# untitled.net
KiCad netlist of a schematic drawn in EAGLE
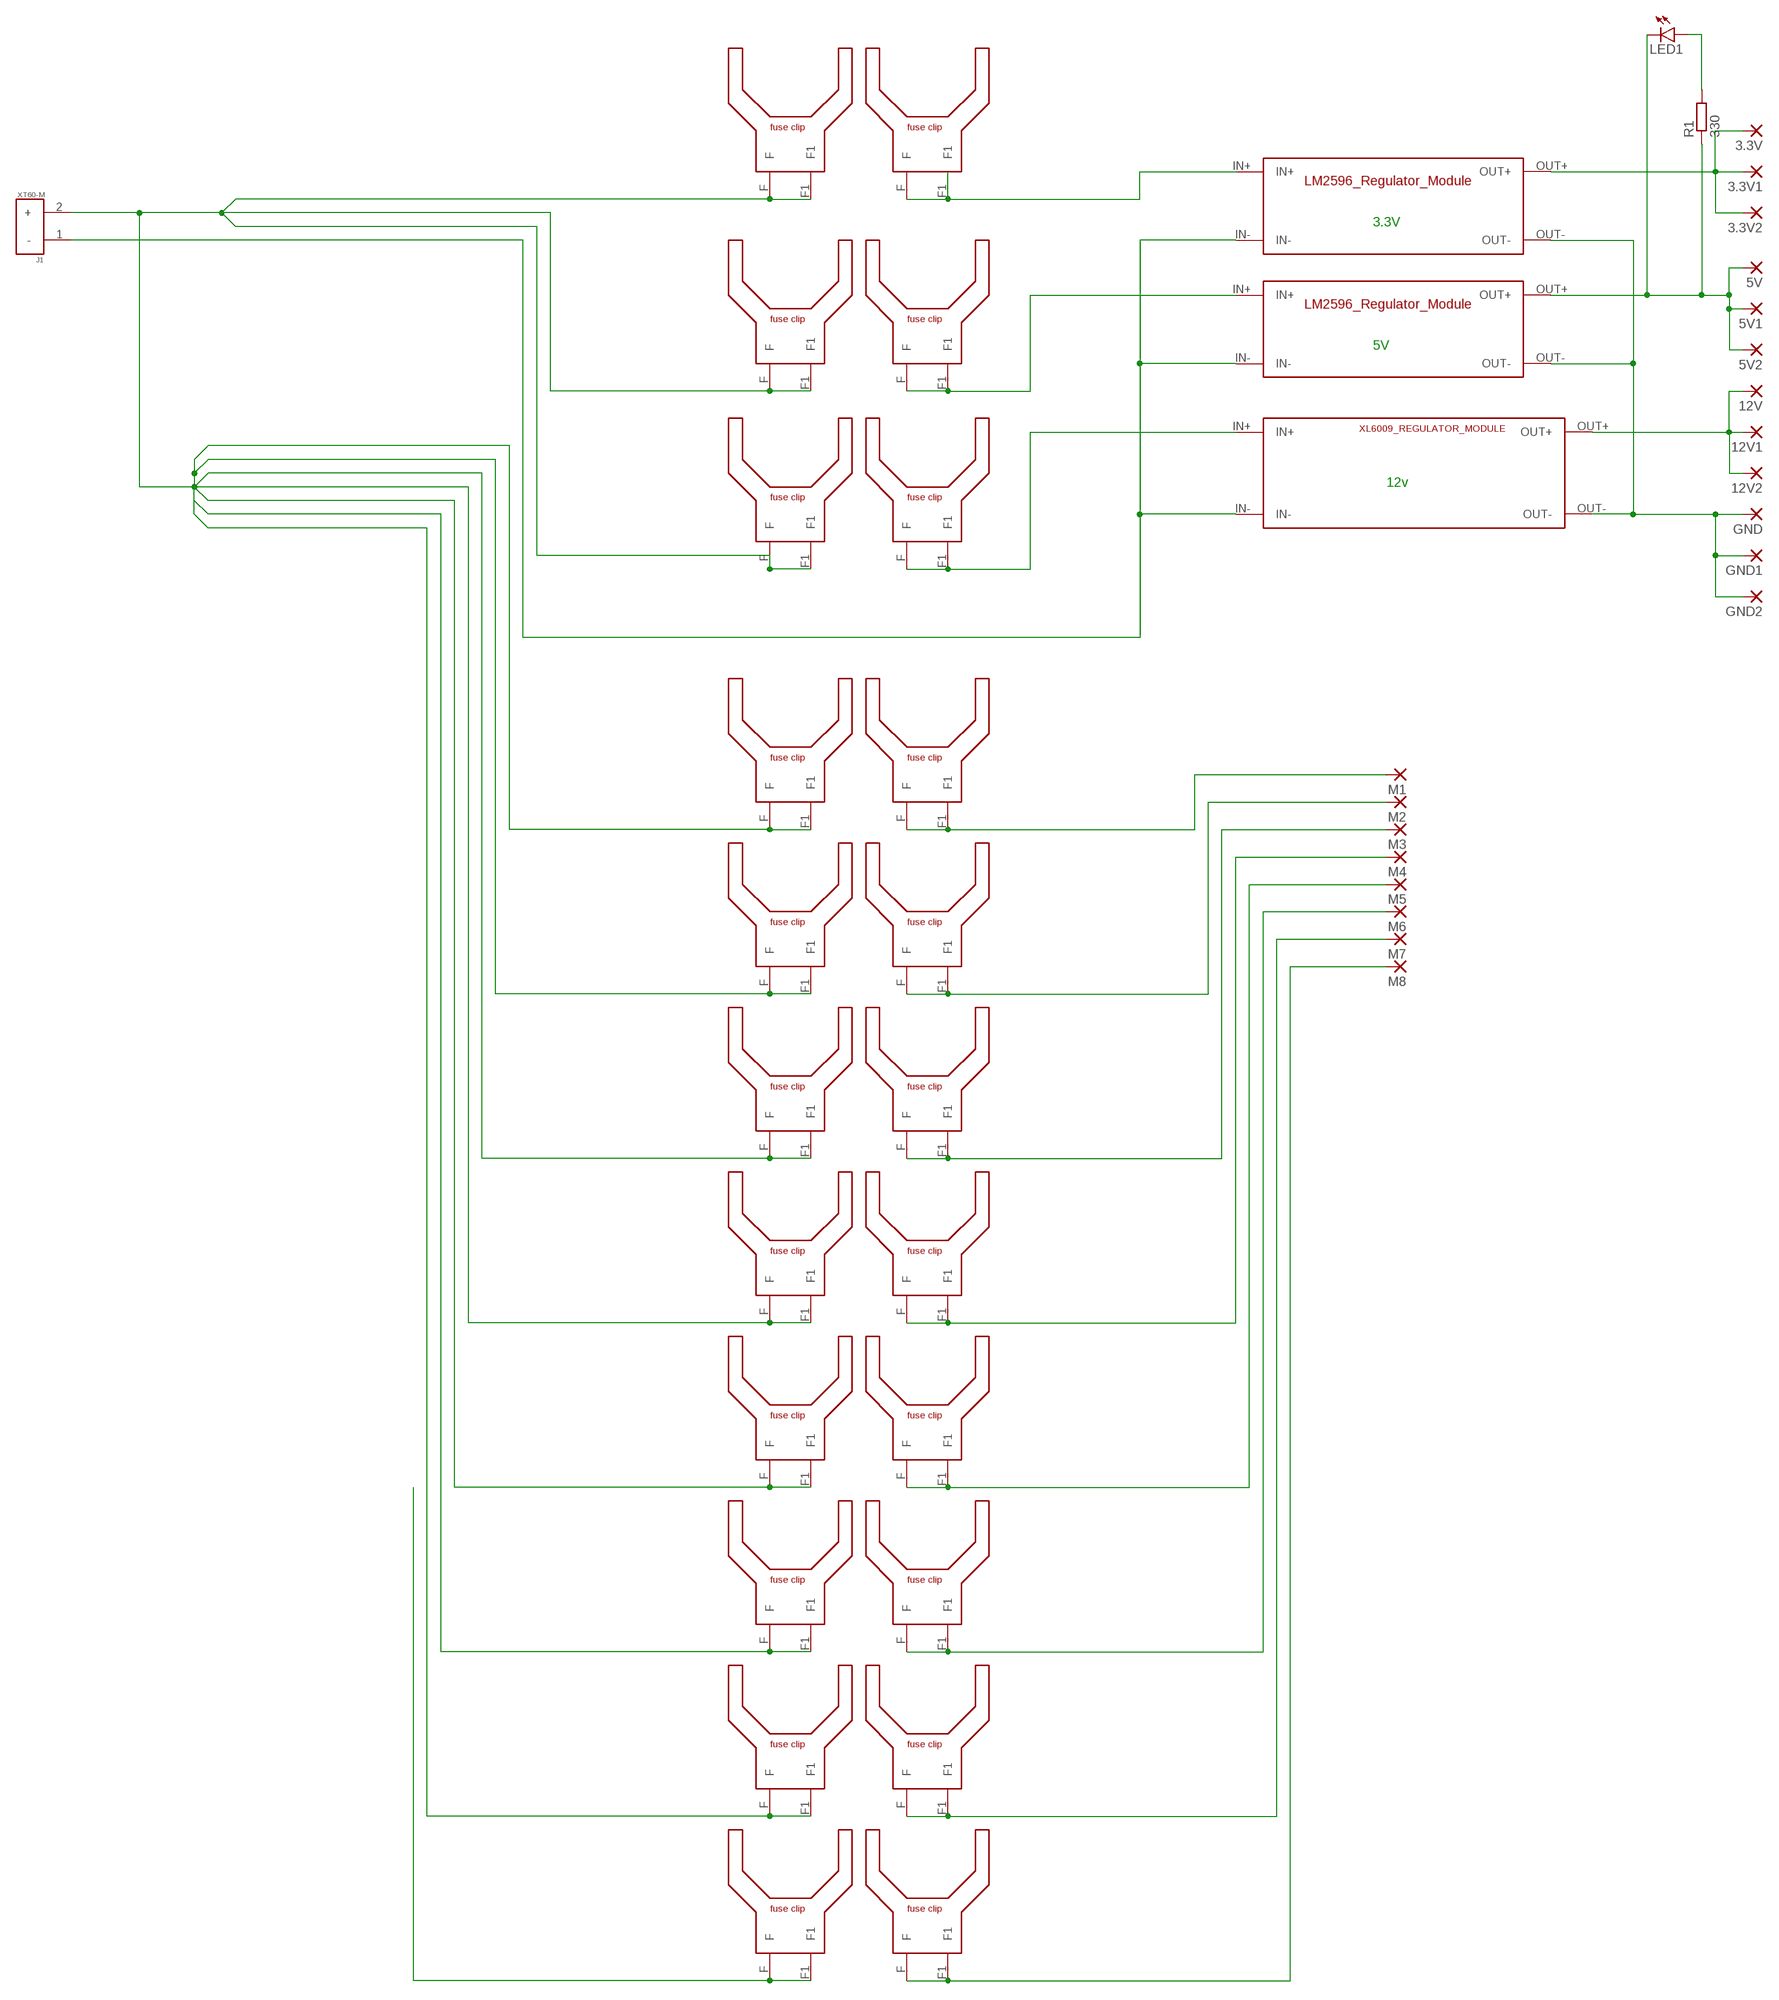
[diagram p0: schematic, sheet 1]

(export (version "E")
  (design (tool "Eeschema 10.0.6"))
  (components
    (comp (ref "3.3V")
      (value "SMD5")
      (footprint "eagle-import:SMD2,54-5,08")
      (libsource (lib "eagle-import") (part "SMD5"))
    )
    (comp (ref "3.3V1")
      (value "SMD5")
      (footprint "eagle-import:SMD2,54-5,08")
      (libsource (lib "eagle-import") (part "SMD5"))
    )
    (comp (ref "3.3V2")
      (value "SMD5")
      (footprint "eagle-import:SMD2,54-5,08")
      (libsource (lib "eagle-import") (part "SMD5"))
    )
    (comp (ref "5V")
      (value "SMD5")
      (footprint "eagle-import:SMD2,54-5,08")
      (libsource (lib "eagle-import") (part "SMD5"))
    )
    (comp (ref "5V1")
      (value "SMD5")
      (footprint "eagle-import:SMD2,54-5,08")
      (libsource (lib "eagle-import") (part "SMD5"))
    )
    (comp (ref "5V2")
      (value "SMD5")
      (footprint "eagle-import:SMD2,54-5,08")
      (libsource (lib "eagle-import") (part "SMD5"))
    )
    (comp (ref "12V")
      (value "SMD5")
      (footprint "eagle-import:SMD2,54-5,08")
      (libsource (lib "eagle-import") (part "SMD5"))
    )
    (comp (ref "12V1")
      (value "SMD5")
      (footprint "eagle-import:SMD2,54-5,08")
      (libsource (lib "eagle-import") (part "SMD5"))
    )
    (comp (ref "12V2")
      (value "SMD5")
      (footprint "eagle-import:SMD2,54-5,08")
      (libsource (lib "eagle-import") (part "SMD5"))
    )
    (comp (ref "GND")
      (value "SMD5")
      (footprint "eagle-import:SMD2,54-5,08")
      (libsource (lib "eagle-import") (part "SMD5"))
    )
    (comp (ref "GND1")
      (value "SMD5")
      (footprint "eagle-import:SMD2,54-5,08")
      (libsource (lib "eagle-import") (part "SMD5"))
    )
    (comp (ref "GND2")
      (value "SMD5")
      (footprint "eagle-import:SMD2,54-5,08")
      (libsource (lib "eagle-import") (part "SMD5"))
    )
    (comp (ref "J1")
      (value "XT60-M")
      (footprint "eagle-import:AMASS_XT60-M")
      (fields (field (name "MF") "AMASS"))
      (libsource (lib "eagle-import") (part "XT60-M"))
    )
    (comp (ref "LED1")
      (value "LED5MM")
      (footprint "eagle-import:LED5MM")
      (libsource (lib "eagle-import") (part "LED5MM"))
    )
    (comp (ref "M1")
      (value "SMD5")
      (footprint "eagle-import:SMD2,54-5,08")
      (libsource (lib "eagle-import") (part "SMD5"))
    )
    (comp (ref "M2")
      (value "SMD5")
      (footprint "eagle-import:SMD2,54-5,08")
      (libsource (lib "eagle-import") (part "SMD5"))
    )
    (comp (ref "M3")
      (value "SMD5")
      (footprint "eagle-import:SMD2,54-5,08")
      (libsource (lib "eagle-import") (part "SMD5"))
    )
    (comp (ref "M4")
      (value "SMD5")
      (footprint "eagle-import:SMD2,54-5,08")
      (libsource (lib "eagle-import") (part "SMD5"))
    )
    (comp (ref "M5")
      (value "SMD5")
      (footprint "eagle-import:SMD2,54-5,08")
      (libsource (lib "eagle-import") (part "SMD5"))
    )
    (comp (ref "M6")
      (value "SMD5")
      (footprint "eagle-import:SMD2,54-5,08")
      (libsource (lib "eagle-import") (part "SMD5"))
    )
    (comp (ref "M7")
      (value "SMD5")
      (footprint "eagle-import:SMD2,54-5,08")
      (libsource (lib "eagle-import") (part "SMD5"))
    )
    (comp (ref "M8")
      (value "SMD5")
      (footprint "eagle-import:SMD2,54-5,08")
      (libsource (lib "eagle-import") (part "SMD5"))
    )
    (comp (ref "R1")
      (value "330")
      (footprint "eagle-import:0207_10")
      (libsource (lib "eagle-import") (part "R-EU_0207/10"))
    )
    (comp (ref "U$1")
      (value "LM2596_MODULE")
      (footprint "eagle-import:LM2596_MODULE")
      (libsource (lib "eagle-import") (part "LM2596_MODULE"))
    )
    (comp (ref "U$2")
      (value "LM2596_MODULE")
      (footprint "eagle-import:LM2596_MODULE")
      (libsource (lib "eagle-import") (part "LM2596_MODULE"))
    )
    (comp (ref "U$3")
      (value "XL6009_MODULE")
      (footprint "eagle-import:XL6009_MODULE")
      (libsource (lib "eagle-import") (part "XL6009_MODULE"))
    )
    (comp (ref "U$4")
      (value "FUSE_HOLDER")
      (footprint "eagle-import:FUSE_HOLDER")
      (libsource (lib "eagle-import") (part "FUSE_HOLDER"))
    )
    (comp (ref "U$5")
      (value "FUSE_HOLDER")
      (footprint "eagle-import:FUSE_HOLDER")
      (libsource (lib "eagle-import") (part "FUSE_HOLDER"))
    )
    (comp (ref "U$6")
      (value "FUSE_HOLDER")
      (footprint "eagle-import:FUSE_HOLDER")
      (libsource (lib "eagle-import") (part "FUSE_HOLDER"))
    )
    (comp (ref "U$7")
      (value "FUSE_HOLDER")
      (footprint "eagle-import:FUSE_HOLDER")
      (libsource (lib "eagle-import") (part "FUSE_HOLDER"))
    )
    (comp (ref "U$8")
      (value "FUSE_HOLDER")
      (footprint "eagle-import:FUSE_HOLDER")
      (libsource (lib "eagle-import") (part "FUSE_HOLDER"))
    )
    (comp (ref "U$9")
      (value "FUSE_HOLDER")
      (footprint "eagle-import:FUSE_HOLDER")
      (libsource (lib "eagle-import") (part "FUSE_HOLDER"))
    )
    (comp (ref "U$10")
      (value "FUSE_HOLDER")
      (footprint "eagle-import:FUSE_HOLDER")
      (libsource (lib "eagle-import") (part "FUSE_HOLDER"))
    )
    (comp (ref "U$11")
      (value "FUSE_HOLDER")
      (footprint "eagle-import:FUSE_HOLDER")
      (libsource (lib "eagle-import") (part "FUSE_HOLDER"))
    )
    (comp (ref "U$12")
      (value "FUSE_HOLDER")
      (footprint "eagle-import:FUSE_HOLDER")
      (libsource (lib "eagle-import") (part "FUSE_HOLDER"))
    )
    (comp (ref "U$13")
      (value "FUSE_HOLDER")
      (footprint "eagle-import:FUSE_HOLDER")
      (libsource (lib "eagle-import") (part "FUSE_HOLDER"))
    )
    (comp (ref "U$14")
      (value "FUSE_HOLDER")
      (footprint "eagle-import:FUSE_HOLDER")
      (libsource (lib "eagle-import") (part "FUSE_HOLDER"))
    )
    (comp (ref "U$15")
      (value "FUSE_HOLDER")
      (footprint "eagle-import:FUSE_HOLDER")
      (libsource (lib "eagle-import") (part "FUSE_HOLDER"))
    )
    (comp (ref "U$16")
      (value "FUSE_HOLDER")
      (footprint "eagle-import:FUSE_HOLDER")
      (libsource (lib "eagle-import") (part "FUSE_HOLDER"))
    )
    (comp (ref "U$17")
      (value "FUSE_HOLDER")
      (footprint "eagle-import:FUSE_HOLDER")
      (libsource (lib "eagle-import") (part "FUSE_HOLDER"))
    )
    (comp (ref "U$18")
      (value "FUSE_HOLDER")
      (footprint "eagle-import:FUSE_HOLDER")
      (libsource (lib "eagle-import") (part "FUSE_HOLDER"))
    )
    (comp (ref "U$19")
      (value "FUSE_HOLDER")
      (footprint "eagle-import:FUSE_HOLDER")
      (libsource (lib "eagle-import") (part "FUSE_HOLDER"))
    )
    (comp (ref "U$20")
      (value "FUSE_HOLDER")
      (footprint "eagle-import:FUSE_HOLDER")
      (libsource (lib "eagle-import") (part "FUSE_HOLDER"))
    )
    (comp (ref "U$21")
      (value "FUSE_HOLDER")
      (footprint "eagle-import:FUSE_HOLDER")
      (libsource (lib "eagle-import") (part "FUSE_HOLDER"))
    )
    (comp (ref "U$22")
      (value "FUSE_HOLDER")
      (footprint "eagle-import:FUSE_HOLDER")
      (libsource (lib "eagle-import") (part "FUSE_HOLDER"))
    )
    (comp (ref "U$23")
      (value "FUSE_HOLDER")
      (footprint "eagle-import:FUSE_HOLDER")
      (libsource (lib "eagle-import") (part "FUSE_HOLDER"))
    )
    (comp (ref "U$24")
      (value "FUSE_HOLDER")
      (footprint "eagle-import:FUSE_HOLDER")
      (libsource (lib "eagle-import") (part "FUSE_HOLDER"))
    )
    (comp (ref "U$25")
      (value "FUSE_HOLDER")
      (footprint "eagle-import:FUSE_HOLDER")
      (libsource (lib "eagle-import") (part "FUSE_HOLDER"))
    )
  )
  (nets
    (net (code "1") (name "Net-(3.3V-P)") (class "Default")
      (node (ref "3.3V") (pin "1") (pinfunction "P_1") (pintype "passive"))
      (node (ref "3.3V1") (pin "1") (pinfunction "P_1") (pintype "passive"))
      (node (ref "3.3V2") (pin "1") (pinfunction "P_1") (pintype "passive"))
      (node (ref "U$1") (pin "OUT+") (pinfunction "OUT+_OUT+") (pintype "bidirectional"))
    )
    (net (code "2") (name "Net-(5V-P)") (class "Default")
      (node (ref "5V") (pin "1") (pinfunction "P_1") (pintype "passive"))
      (node (ref "5V1") (pin "1") (pinfunction "P_1") (pintype "passive"))
      (node (ref "5V2") (pin "1") (pinfunction "P_1") (pintype "passive"))
      (node (ref "LED1") (pin "K") (pinfunction "C_K") (pintype "passive"))
      (node (ref "R1") (pin "1") (pinfunction "1_1") (pintype "passive"))
      (node (ref "U$2") (pin "OUT+") (pinfunction "OUT+_OUT+") (pintype "bidirectional"))
    )
    (net (code "3") (name "Net-(12V-P)") (class "Default")
      (node (ref "12V") (pin "1") (pinfunction "P_1") (pintype "passive"))
      (node (ref "12V1") (pin "1") (pinfunction "P_1") (pintype "passive"))
      (node (ref "12V2") (pin "1") (pinfunction "P_1") (pintype "passive"))
      (node (ref "U$3") (pin "OUT+") (pinfunction "OUT+_OUT+") (pintype "bidirectional"))
    )
    (net (code "4") (name "Net-(GND-P)") (class "Default")
      (node (ref "GND") (pin "1") (pinfunction "P_1") (pintype "passive"))
      (node (ref "GND1") (pin "1") (pinfunction "P_1") (pintype "passive"))
      (node (ref "GND2") (pin "1") (pinfunction "P_1") (pintype "passive"))
      (node (ref "U$1") (pin "OUT-") (pinfunction "OUT-_OUT-") (pintype "bidirectional"))
      (node (ref "U$2") (pin "OUT-") (pinfunction "OUT-_OUT-") (pintype "bidirectional"))
      (node (ref "U$3") (pin "OUT-") (pinfunction "OUT-_OUT-") (pintype "bidirectional"))
    )
    (net (code "5") (name "Net-(J1-+)") (class "Default")
      (node (ref "J1") (pin "2") (pinfunction "+_2") (pintype "passive"))
      (node (ref "U$10") (pin "F") (pinfunction "F_F") (pintype "bidirectional"))
      (node (ref "U$10") (pin "F1") (pinfunction "F1_F1") (pintype "bidirectional"))
      (node (ref "U$12") (pin "F") (pinfunction "F_F") (pintype "bidirectional"))
      (node (ref "U$12") (pin "F1") (pinfunction "F1_F1") (pintype "bidirectional"))
      (node (ref "U$14") (pin "F") (pinfunction "F_F") (pintype "bidirectional"))
      (node (ref "U$14") (pin "F1") (pinfunction "F1_F1") (pintype "bidirectional"))
      (node (ref "U$16") (pin "F") (pinfunction "F_F") (pintype "bidirectional"))
      (node (ref "U$16") (pin "F1") (pinfunction "F1_F1") (pintype "bidirectional"))
      (node (ref "U$18") (pin "F") (pinfunction "F_F") (pintype "bidirectional"))
      (node (ref "U$18") (pin "F1") (pinfunction "F1_F1") (pintype "bidirectional"))
      (node (ref "U$20") (pin "F") (pinfunction "F_F") (pintype "bidirectional"))
      (node (ref "U$20") (pin "F1") (pinfunction "F1_F1") (pintype "bidirectional"))
      (node (ref "U$22") (pin "F") (pinfunction "F_F") (pintype "bidirectional"))
      (node (ref "U$22") (pin "F1") (pinfunction "F1_F1") (pintype "bidirectional"))
      (node (ref "U$5") (pin "F") (pinfunction "F_F") (pintype "bidirectional"))
      (node (ref "U$5") (pin "F1") (pinfunction "F1_F1") (pintype "bidirectional"))
      (node (ref "U$7") (pin "F") (pinfunction "F_F") (pintype "bidirectional"))
      (node (ref "U$7") (pin "F1") (pinfunction "F1_F1") (pintype "bidirectional"))
      (node (ref "U$9") (pin "F") (pinfunction "F_F") (pintype "bidirectional"))
      (node (ref "U$9") (pin "F1") (pinfunction "F1_F1") (pintype "bidirectional"))
    )
    (net (code "6") (name "Net-(J1--)") (class "Default")
      (node (ref "J1") (pin "1") (pinfunction "-_1") (pintype "passive"))
      (node (ref "U$1") (pin "IN-") (pinfunction "IN-_IN-") (pintype "bidirectional"))
      (node (ref "U$2") (pin "IN-") (pinfunction "IN-_IN-") (pintype "bidirectional"))
      (node (ref "U$3") (pin "IN-") (pinfunction "IN-_IN-") (pintype "bidirectional"))
    )
    (net (code "7") (name "Net-(LED1-PadA)") (class "Default")
      (node (ref "LED1") (pin "A") (pinfunction "A_A") (pintype "passive"))
      (node (ref "R1") (pin "2") (pinfunction "2_2") (pintype "passive"))
    )
    (net (code "8") (name "Net-(M1-P)") (class "Default")
      (node (ref "M1") (pin "1") (pinfunction "P_1") (pintype "passive"))
      (node (ref "U$11") (pin "F") (pinfunction "F_F") (pintype "bidirectional"))
      (node (ref "U$11") (pin "F1") (pinfunction "F1_F1") (pintype "bidirectional"))
    )
    (net (code "9") (name "Net-(M2-P)") (class "Default")
      (node (ref "M2") (pin "1") (pinfunction "P_1") (pintype "passive"))
      (node (ref "U$13") (pin "F") (pinfunction "F_F") (pintype "bidirectional"))
      (node (ref "U$13") (pin "F1") (pinfunction "F1_F1") (pintype "bidirectional"))
    )
    (net (code "10") (name "Net-(M3-P)") (class "Default")
      (node (ref "M3") (pin "1") (pinfunction "P_1") (pintype "passive"))
      (node (ref "U$15") (pin "F") (pinfunction "F_F") (pintype "bidirectional"))
      (node (ref "U$15") (pin "F1") (pinfunction "F1_F1") (pintype "bidirectional"))
    )
    (net (code "11") (name "Net-(M4-P)") (class "Default")
      (node (ref "M4") (pin "1") (pinfunction "P_1") (pintype "passive"))
      (node (ref "U$17") (pin "F") (pinfunction "F_F") (pintype "bidirectional"))
      (node (ref "U$17") (pin "F1") (pinfunction "F1_F1") (pintype "bidirectional"))
    )
    (net (code "12") (name "Net-(M5-P)") (class "Default")
      (node (ref "M5") (pin "1") (pinfunction "P_1") (pintype "passive"))
      (node (ref "U$19") (pin "F") (pinfunction "F_F") (pintype "bidirectional"))
      (node (ref "U$19") (pin "F1") (pinfunction "F1_F1") (pintype "bidirectional"))
    )
    (net (code "13") (name "Net-(M6-P)") (class "Default")
      (node (ref "M6") (pin "1") (pinfunction "P_1") (pintype "passive"))
      (node (ref "U$21") (pin "F") (pinfunction "F_F") (pintype "bidirectional"))
      (node (ref "U$21") (pin "F1") (pinfunction "F1_F1") (pintype "bidirectional"))
    )
    (net (code "14") (name "Net-(M7-P)") (class "Default")
      (node (ref "M7") (pin "1") (pinfunction "P_1") (pintype "passive"))
      (node (ref "U$23") (pin "F") (pinfunction "F_F") (pintype "bidirectional"))
      (node (ref "U$23") (pin "F1") (pinfunction "F1_F1") (pintype "bidirectional"))
    )
    (net (code "15") (name "Net-(M8-P)") (class "Default")
      (node (ref "M8") (pin "1") (pinfunction "P_1") (pintype "passive"))
      (node (ref "U$25") (pin "F") (pinfunction "F_F") (pintype "bidirectional"))
      (node (ref "U$25") (pin "F1") (pinfunction "F1_F1") (pintype "bidirectional"))
    )
    (net (code "16") (name "Net-(U$1-PadIN+)") (class "Default")
      (node (ref "U$1") (pin "IN+") (pinfunction "IN+_IN+") (pintype "bidirectional"))
      (node (ref "U$4") (pin "F") (pinfunction "F_F") (pintype "bidirectional"))
      (node (ref "U$4") (pin "F1") (pinfunction "F1_F1") (pintype "bidirectional"))
    )
    (net (code "17") (name "Net-(U$2-PadIN+)") (class "Default")
      (node (ref "U$2") (pin "IN+") (pinfunction "IN+_IN+") (pintype "bidirectional"))
      (node (ref "U$6") (pin "F") (pinfunction "F_F") (pintype "bidirectional"))
      (node (ref "U$6") (pin "F1") (pinfunction "F1_F1") (pintype "bidirectional"))
    )
    (net (code "18") (name "Net-(U$3-PadIN+)") (class "Default")
      (node (ref "U$3") (pin "IN+") (pinfunction "IN+_IN+") (pintype "bidirectional"))
      (node (ref "U$8") (pin "F") (pinfunction "F_F") (pintype "bidirectional"))
      (node (ref "U$8") (pin "F1") (pinfunction "F1_F1") (pintype "bidirectional"))
    )
    (net (code "19") (name "Net-(U$24-PadF)") (class "Default")
      (node (ref "U$24") (pin "F") (pinfunction "F_F") (pintype "bidirectional"))
      (node (ref "U$24") (pin "F1") (pinfunction "F1_F1") (pintype "bidirectional"))
    )
  )
)
